# USB_Input.net
KiCad netlist of a schematic drawn in Altium Designer
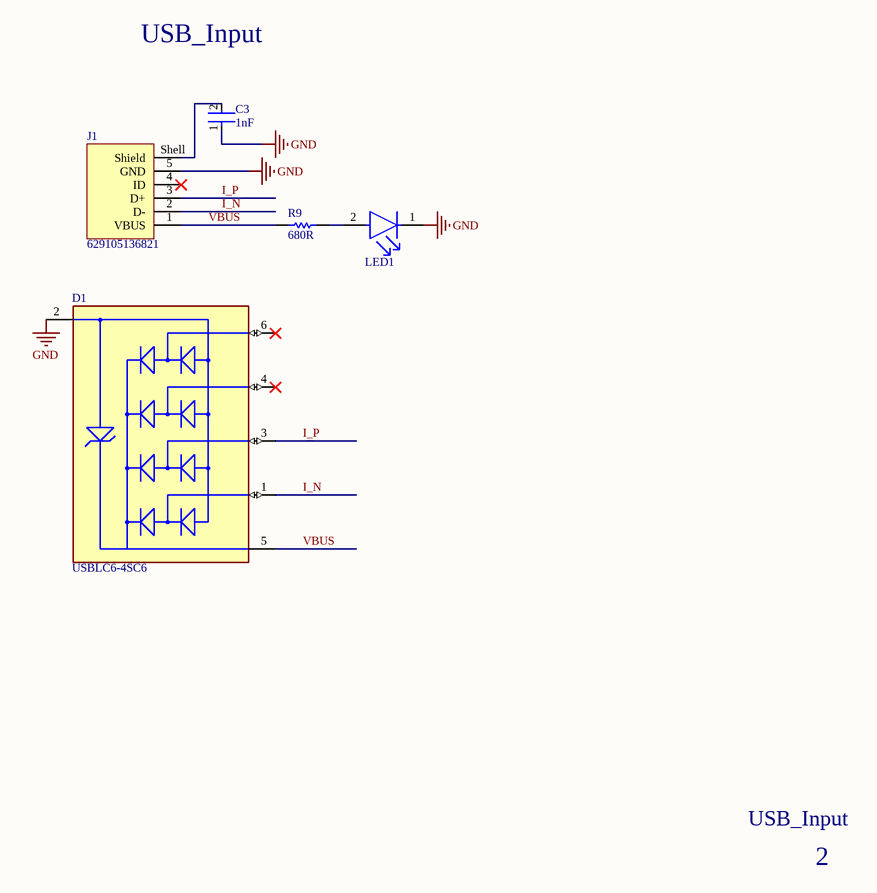
[diagram p0: USB_Input.SchDoc]

(export (version "E")
  (design (tool "Eeschema 10.0.6"))
  (components
    (comp (ref "C3")
      (value "1nF")
      (footprint "FP-CC0603-DA-MFG")
      (description "CAP CER 1000PF 50V X7R 0603")
      (fields
        (field (name "MANUFACTURER PART NUMBER") "CC0603KRX7R9BB102")
        (field (name "MANUFACTURER") "YAGEO")
      )
      (libsource (lib "Altium Content Vault") (part "11868f565c42a9108669ba33697ecf6"))
    )
    (comp (ref "D1")
      (value "USBLC6-4SC6")
      (footprint "FP-SOT23-6L-MFG")
      (description "TVS DIODE 5.25V 17V SOT23-6")
      (fields
        (field (name "MANUFACTURER") "STMicroelectronics")
        (field (name "OCTOPART") "https://octopart.com/usblc6-4sc6-stmicroelectronics-347147")
      )
      (libsource (lib "Altium Content Vault") (part "3e70b616ccdc4c88b528e1820c4a7da"))
    )
    (comp (ref "J1")
      (value "629105136821")
      (footprint "629105136821")
      (libsource (lib "Altium Content Vault") (part "Micro USB 2.0_Type B_Receptacle_1 Port"))
    )
    (comp (ref "LED1")
      (value "LS R976-NR-1")
      (footprint "FP-LS_R976-MFG")
      (description "LED RED DIFFUSED 0805 SMD")
      (libsource (lib "Altium Content Vault") (part "8706943c75ba83719d021d2fdc84c58"))
    )
    (comp (ref "R9")
      (value "680R")
      (footprint "RESC1608X55X30ML20T20")
      (fields (field (name "MANUFACTURER") "Panasonic") (field (name "PART NUMBER") "ERA-3AEB681V"))
      (libsource (lib "Altium Content Vault") (part "RES"))
    )
  )
  (nets
    (net (code "1") (name "/I_N") (class "Default")
      (node (ref "D1") (pin "1") (pinfunction "I/O1_1") (pintype "bidirectional"))
      (node (ref "J1") (pin "2") (pinfunction "D-_2") (pintype "passive"))
    )
    (net (code "2") (name "/I_P") (class "Default")
      (node (ref "D1") (pin "3") (pinfunction "I/O2_3") (pintype "bidirectional"))
      (node (ref "J1") (pin "3") (pinfunction "D+_3") (pintype "passive"))
    )
    (net (code "3") (name "/VBUS") (class "Default")
      (node (ref "D1") (pin "5") (pinfunction "VBUS_5") (pintype "power_in"))
      (node (ref "J1") (pin "1") (pinfunction "VBUS_1") (pintype "passive"))
      (node (ref "R9") (pin "2") (pinfunction "2_2") (pintype "passive"))
    )
    (net (code "4") (name "GND") (class "Default")
      (node (ref "C3") (pin "1") (pinfunction "1_1") (pintype "passive"))
      (node (ref "D1") (pin "2") (pinfunction "GND_2") (pintype "power_in"))
      (node (ref "J1") (pin "5") (pinfunction "GND_5") (pintype "passive"))
      (node (ref "LED1") (pin "1") (pinfunction "C_1") (pintype "passive"))
    )
    (net (code "5") (name "Net-(J1-Shield)") (class "Default")
      (node (ref "C3") (pin "2") (pinfunction "2_2") (pintype "passive"))
      (node (ref "J1") (pin "Shell") (pinfunction "Shield_Shell") (pintype "passive"))
    )
    (net (code "6") (name "Net-(LED1-A)") (class "Default")
      (node (ref "LED1") (pin "2") (pinfunction "A_2") (pintype "passive"))
      (node (ref "R9") (pin "1") (pinfunction "1_1") (pintype "passive"))
    )
    (net (code "7") (name "unconnected-(D1-I{slash}O3-Pad4)") (class "Default")
      (node (ref "D1") (pin "4") (pinfunction "I/O3_4") (pintype "bidirectional+no_connect"))
    )
    (net (code "8") (name "unconnected-(D1-I{slash}O4-Pad6)") (class "Default")
      (node (ref "D1") (pin "6") (pinfunction "I/O4_6") (pintype "bidirectional+no_connect"))
    )
    (net (code "9") (name "unconnected-(J1-ID-Pad4)") (class "Default")
      (node (ref "J1") (pin "4") (pinfunction "ID_4") (pintype "passive+no_connect"))
    )
  )
)
